# ParticleCounter.net
KiCad netlist of a schematic drawn in EAGLE
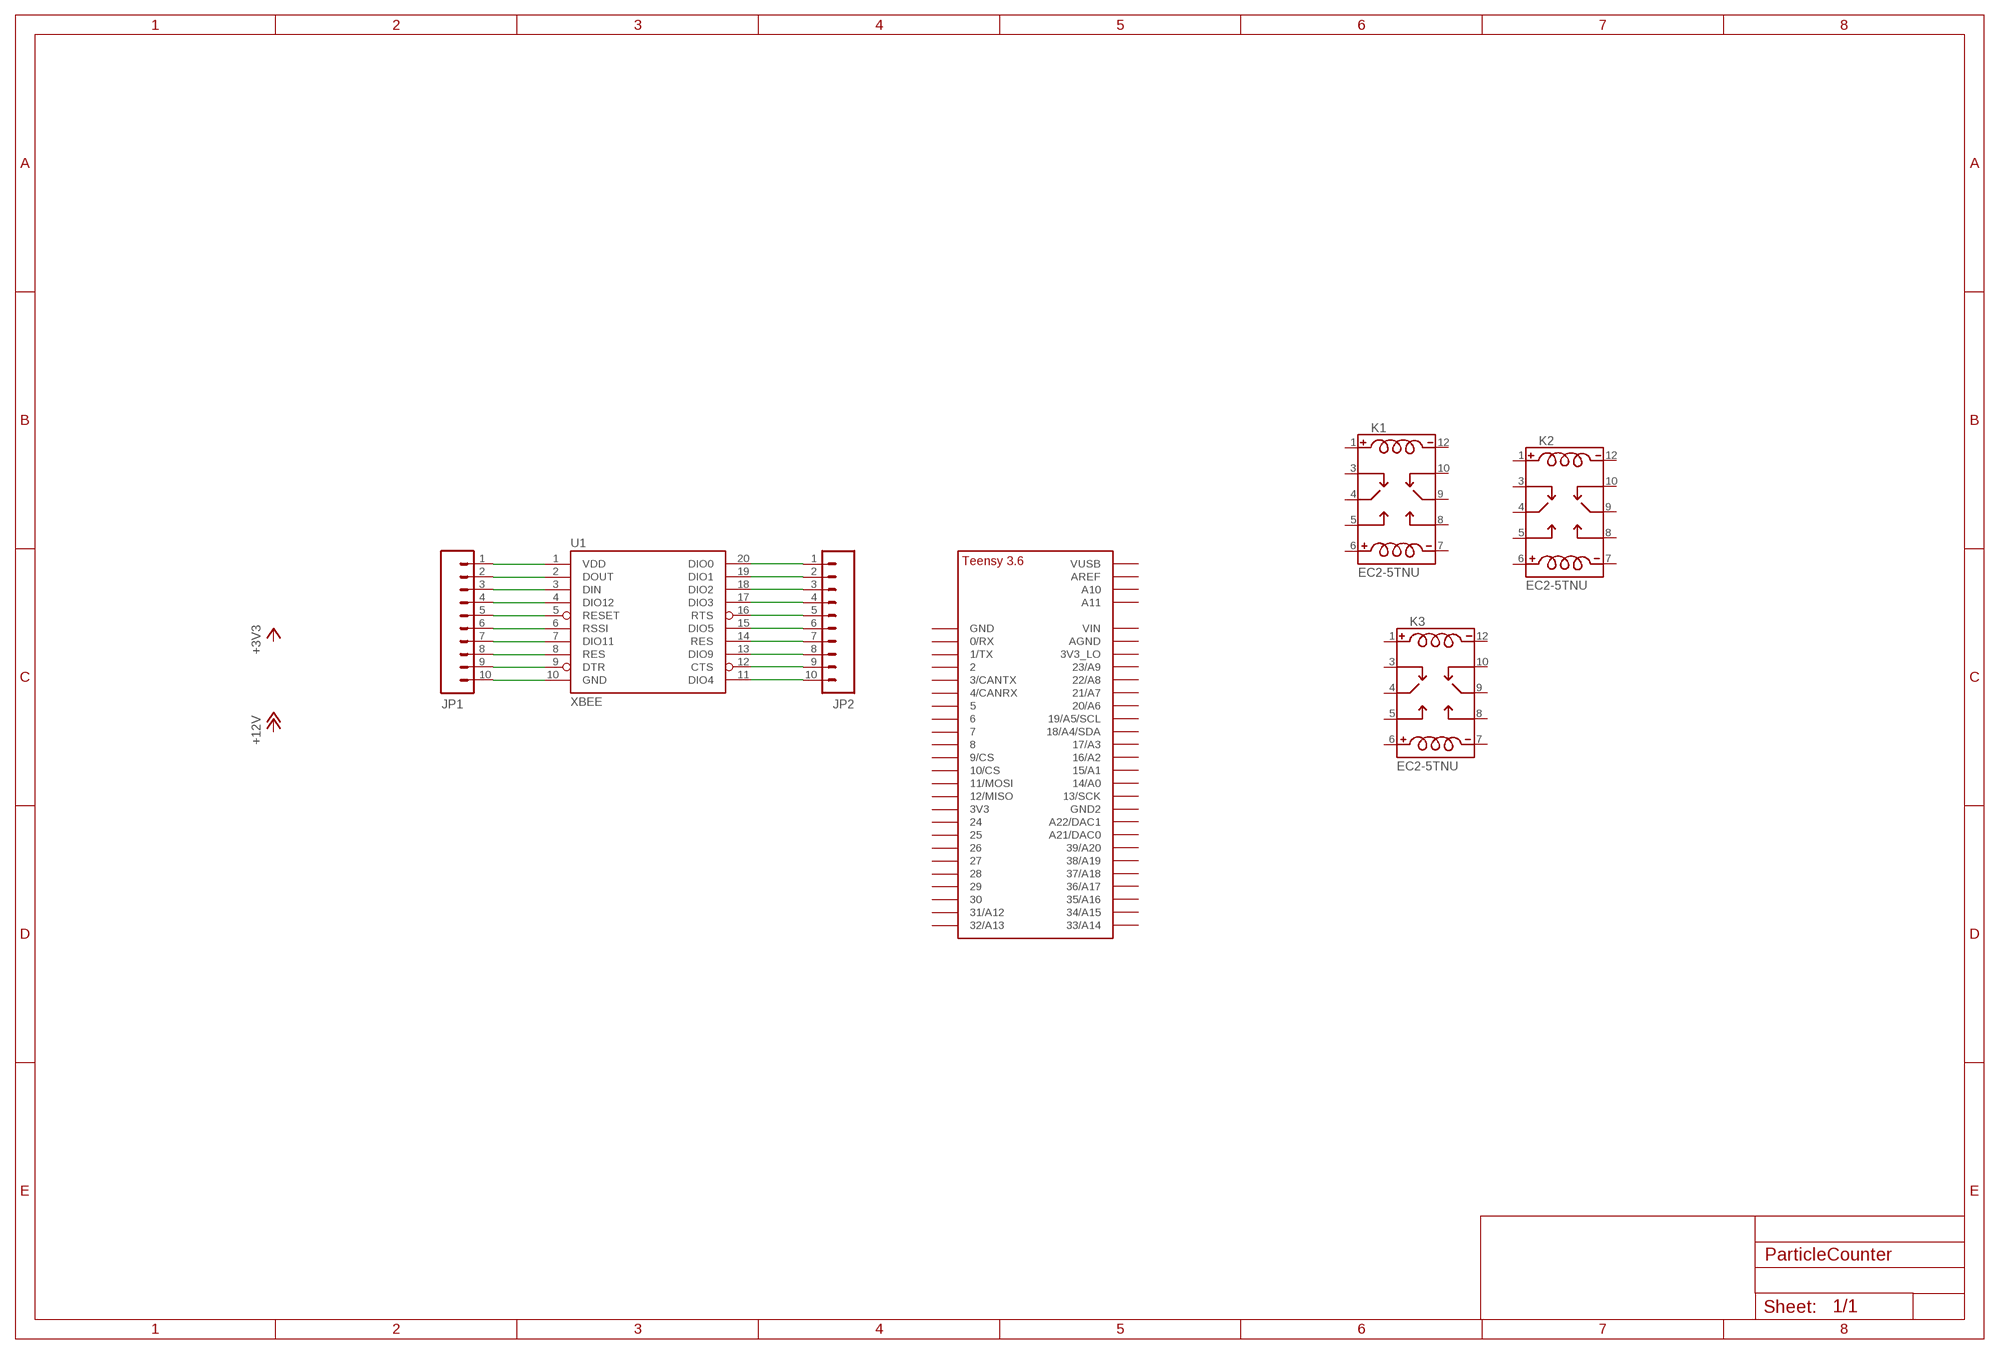
[diagram p0: schematic, sheet 1]

(export (version "E")
  (design (tool "Eeschema 10.0.6"))
  (components
    (comp (ref "JP1")
      (value "M100.1")
      (footprint "eagle-import:1X10")
      (libsource (lib "eagle-import") (part "M100.1"))
    )
    (comp (ref "JP2")
      (value "M100.1")
      (footprint "eagle-import:1X10")
      (libsource (lib "eagle-import") (part "M100.1"))
    )
    (comp (ref "K1")
      (value "EC2-5TNU")
      (footprint "eagle-import:RELAY_EC2-5TNU")
      (fields (field (name "MF") "KEMET"))
      (libsource (lib "eagle-import") (part "EC2-5TNU"))
    )
    (comp (ref "K2")
      (value "EC2-5TNU")
      (footprint "eagle-import:RELAY_EC2-5TNU")
      (fields (field (name "MF") "KEMET"))
      (libsource (lib "eagle-import") (part "EC2-5TNU"))
    )
    (comp (ref "K3")
      (value "EC2-5TNU")
      (footprint "eagle-import:RELAY_EC2-5TNU")
      (fields (field (name "MF") "KEMET"))
      (libsource (lib "eagle-import") (part "EC2-5TNU"))
    )
    (comp (ref "U$1")
      (value "TEENSY_3.5/3.6_BASIC")
      (footprint "eagle-import:TEENSY_3.5_3.6_BASIC")
      (libsource (lib "eagle-import") (part "TEENSY_3.5/3.6_BASIC"))
    )
    (comp (ref "U1")
      (value "XBEE")
      (footprint "eagle-import:XBEE-1")
      (libsource (lib "eagle-import") (part "XBEE-1B1"))
    )
  )
  (nets
    (net (code "3") (name "Net-(JP1-Pad8)") (class "Default")
      (node (ref "JP1") (pin "8") (pinfunction "8_8") (pintype "passive"))
      (node (ref "U1") (pin "8") (pinfunction "RES_8") (pintype "bidirectional"))
    )
    (net (code "4") (name "Net-(JP2-Pad7)") (class "Default")
      (node (ref "JP2") (pin "7") (pinfunction "7_7") (pintype "passive"))
      (node (ref "U1") (pin "14") (pinfunction "RES_14") (pintype "bidirectional"))
    )
    (net (code "5") (name "Net-(U1-CTS)") (class "Default")
      (node (ref "JP2") (pin "9") (pinfunction "9_9") (pintype "passive"))
      (node (ref "U1") (pin "12") (pinfunction "CTS_12") (pintype "output"))
    )
    (net (code "6") (name "Net-(U1-DIN)") (class "Default")
      (node (ref "JP1") (pin "3") (pinfunction "3_3") (pintype "passive"))
      (node (ref "U1") (pin "3") (pinfunction "DIN_3") (pintype "input"))
    )
    (net (code "7") (name "Net-(U1-DIO0)") (class "Default")
      (node (ref "JP2") (pin "1") (pinfunction "1_1") (pintype "passive"))
      (node (ref "U1") (pin "20") (pinfunction "DIO0_20") (pintype "bidirectional"))
    )
    (net (code "8") (name "Net-(U1-DIO1)") (class "Default")
      (node (ref "JP2") (pin "2") (pinfunction "2_2") (pintype "passive"))
      (node (ref "U1") (pin "19") (pinfunction "DIO1_19") (pintype "bidirectional"))
    )
    (net (code "9") (name "Net-(U1-DIO2)") (class "Default")
      (node (ref "JP2") (pin "3") (pinfunction "3_3") (pintype "passive"))
      (node (ref "U1") (pin "18") (pinfunction "DIO2_18") (pintype "bidirectional"))
    )
    (net (code "10") (name "Net-(U1-DIO3)") (class "Default")
      (node (ref "JP2") (pin "4") (pinfunction "4_4") (pintype "passive"))
      (node (ref "U1") (pin "17") (pinfunction "DIO3_17") (pintype "bidirectional"))
    )
    (net (code "11") (name "Net-(U1-DIO4)") (class "Default")
      (node (ref "JP2") (pin "10") (pinfunction "10_10") (pintype "passive"))
      (node (ref "U1") (pin "11") (pinfunction "DIO4_11") (pintype "bidirectional"))
    )
    (net (code "12") (name "Net-(U1-DIO5)") (class "Default")
      (node (ref "JP2") (pin "6") (pinfunction "6_6") (pintype "passive"))
      (node (ref "U1") (pin "15") (pinfunction "DIO5_15") (pintype "bidirectional"))
    )
    (net (code "13") (name "Net-(U1-DIO9)") (class "Default")
      (node (ref "JP2") (pin "8") (pinfunction "8_8") (pintype "passive"))
      (node (ref "U1") (pin "13") (pinfunction "DIO9_13") (pintype "bidirectional"))
    )
    (net (code "14") (name "Net-(U1-DIO11)") (class "Default")
      (node (ref "JP1") (pin "7") (pinfunction "7_7") (pintype "passive"))
      (node (ref "U1") (pin "7") (pinfunction "DIO11_7") (pintype "bidirectional"))
    )
    (net (code "15") (name "Net-(U1-DIO12)") (class "Default")
      (node (ref "JP1") (pin "4") (pinfunction "4_4") (pintype "passive"))
      (node (ref "U1") (pin "4") (pinfunction "DIO12_4") (pintype "bidirectional"))
    )
    (net (code "16") (name "Net-(U1-DOUT)") (class "Default")
      (node (ref "JP1") (pin "2") (pinfunction "2_2") (pintype "passive"))
      (node (ref "U1") (pin "2") (pinfunction "DOUT_2") (pintype "output"))
    )
    (net (code "17") (name "Net-(U1-DTR)") (class "Default")
      (node (ref "JP1") (pin "9") (pinfunction "9_9") (pintype "passive"))
      (node (ref "U1") (pin "9") (pinfunction "DTR_9") (pintype "bidirectional"))
    )
    (net (code "18") (name "Net-(U1-GND)") (class "Default")
      (node (ref "JP1") (pin "10") (pinfunction "10_10") (pintype "passive"))
      (node (ref "U1") (pin "10") (pinfunction "GND_10") (pintype "power_in"))
    )
    (net (code "19") (name "Net-(U1-RESET)") (class "Default")
      (node (ref "JP1") (pin "5") (pinfunction "5_5") (pintype "passive"))
      (node (ref "U1") (pin "5") (pinfunction "RESET_5") (pintype "input"))
    )
    (net (code "20") (name "Net-(U1-RSSI)") (class "Default")
      (node (ref "JP1") (pin "6") (pinfunction "6_6") (pintype "passive"))
      (node (ref "U1") (pin "6") (pinfunction "RSSI_6") (pintype "bidirectional"))
    )
    (net (code "21") (name "Net-(U1-RTS)") (class "Default")
      (node (ref "JP2") (pin "5") (pinfunction "5_5") (pintype "passive"))
      (node (ref "U1") (pin "16") (pinfunction "RTS_16") (pintype "input"))
    )
    (net (code "22") (name "Net-(U1-VDD)") (class "Default")
      (node (ref "JP1") (pin "1") (pinfunction "1_1") (pintype "passive"))
      (node (ref "U1") (pin "1") (pinfunction "VDD_1") (pintype "power_in"))
    )
    (net (code "23") (name "unconnected-(K1-C1-Pad1)") (class "Default")
      (node (ref "K1") (pin "1") (pinfunction "C1_1") (pintype "passive"))
    )
    (net (code "24") (name "unconnected-(K1-C2-Pad12)") (class "Default")
      (node (ref "K1") (pin "12") (pinfunction "C2_12") (pintype "passive"))
    )
    (net (code "25") (name "unconnected-(K1-C3-Pad6)") (class "Default")
      (node (ref "K1") (pin "6") (pinfunction "C3_6") (pintype "passive"))
    )
    (net (code "26") (name "unconnected-(K1-C4-Pad7)") (class "Default")
      (node (ref "K1") (pin "7") (pinfunction "C4_7") (pintype "passive"))
    )
    (net (code "27") (name "unconnected-(K1-M-Pad9)") (class "Default")
      (node (ref "K1") (pin "9") (pinfunction "M_9") (pintype "passive"))
    )
    (net (code "28") (name "unconnected-(K1-M1-Pad4)") (class "Default")
      (node (ref "K1") (pin "4") (pinfunction "M1_4") (pintype "passive"))
    )
    (net (code "29") (name "unconnected-(K1-NC-Pad10)") (class "Default")
      (node (ref "K1") (pin "10") (pinfunction "NC_10") (pintype "passive"))
    )
    (net (code "30") (name "unconnected-(K1-NC1-Pad3)") (class "Default")
      (node (ref "K1") (pin "3") (pinfunction "NC1_3") (pintype "passive"))
    )
    (net (code "31") (name "unconnected-(K1-NO-Pad8)") (class "Default")
      (node (ref "K1") (pin "8") (pinfunction "NO_8") (pintype "passive"))
    )
    (net (code "32") (name "unconnected-(K1-NO1-Pad5)") (class "Default")
      (node (ref "K1") (pin "5") (pinfunction "NO1_5") (pintype "passive"))
    )
    (net (code "33") (name "unconnected-(K2-C1-Pad1)") (class "Default")
      (node (ref "K2") (pin "1") (pinfunction "C1_1") (pintype "passive"))
    )
    (net (code "34") (name "unconnected-(K2-C2-Pad12)") (class "Default")
      (node (ref "K2") (pin "12") (pinfunction "C2_12") (pintype "passive"))
    )
    (net (code "35") (name "unconnected-(K2-C3-Pad6)") (class "Default")
      (node (ref "K2") (pin "6") (pinfunction "C3_6") (pintype "passive"))
    )
    (net (code "36") (name "unconnected-(K2-C4-Pad7)") (class "Default")
      (node (ref "K2") (pin "7") (pinfunction "C4_7") (pintype "passive"))
    )
    (net (code "37") (name "unconnected-(K2-M-Pad9)") (class "Default")
      (node (ref "K2") (pin "9") (pinfunction "M_9") (pintype "passive"))
    )
    (net (code "38") (name "unconnected-(K2-M1-Pad4)") (class "Default")
      (node (ref "K2") (pin "4") (pinfunction "M1_4") (pintype "passive"))
    )
    (net (code "39") (name "unconnected-(K2-NC-Pad10)") (class "Default")
      (node (ref "K2") (pin "10") (pinfunction "NC_10") (pintype "passive"))
    )
    (net (code "40") (name "unconnected-(K2-NC1-Pad3)") (class "Default")
      (node (ref "K2") (pin "3") (pinfunction "NC1_3") (pintype "passive"))
    )
    (net (code "41") (name "unconnected-(K2-NO-Pad8)") (class "Default")
      (node (ref "K2") (pin "8") (pinfunction "NO_8") (pintype "passive"))
    )
    (net (code "42") (name "unconnected-(K2-NO1-Pad5)") (class "Default")
      (node (ref "K2") (pin "5") (pinfunction "NO1_5") (pintype "passive"))
    )
    (net (code "43") (name "unconnected-(K3-C1-Pad1)") (class "Default")
      (node (ref "K3") (pin "1") (pinfunction "C1_1") (pintype "passive"))
    )
    (net (code "44") (name "unconnected-(K3-C2-Pad12)") (class "Default")
      (node (ref "K3") (pin "12") (pinfunction "C2_12") (pintype "passive"))
    )
    (net (code "45") (name "unconnected-(K3-C3-Pad6)") (class "Default")
      (node (ref "K3") (pin "6") (pinfunction "C3_6") (pintype "passive"))
    )
    (net (code "46") (name "unconnected-(K3-C4-Pad7)") (class "Default")
      (node (ref "K3") (pin "7") (pinfunction "C4_7") (pintype "passive"))
    )
    (net (code "47") (name "unconnected-(K3-M-Pad9)") (class "Default")
      (node (ref "K3") (pin "9") (pinfunction "M_9") (pintype "passive"))
    )
    (net (code "48") (name "unconnected-(K3-M1-Pad4)") (class "Default")
      (node (ref "K3") (pin "4") (pinfunction "M1_4") (pintype "passive"))
    )
    (net (code "49") (name "unconnected-(K3-NC-Pad10)") (class "Default")
      (node (ref "K3") (pin "10") (pinfunction "NC_10") (pintype "passive"))
    )
    (net (code "50") (name "unconnected-(K3-NC1-Pad3)") (class "Default")
      (node (ref "K3") (pin "3") (pinfunction "NC1_3") (pintype "passive"))
    )
    (net (code "51") (name "unconnected-(K3-NO-Pad8)") (class "Default")
      (node (ref "K3") (pin "8") (pinfunction "NO_8") (pintype "passive"))
    )
    (net (code "52") (name "unconnected-(K3-NO1-Pad5)") (class "Default")
      (node (ref "K3") (pin "5") (pinfunction "NO1_5") (pintype "passive"))
    )
    (net (code "53") (name "unconnected-(U$1-A21{slash}DAC0-Pad21{slash}DAC0)") (class "Default")
      (node (ref "U$1") (pin "21/DAC0") (pinfunction "A21/DAC0_21/DAC0") (pintype "bidirectional"))
    )
    (net (code "54") (name "unconnected-(U$1-Pad0{slash}RX)") (class "Default")
      (node (ref "U$1") (pin "0/RX") (pinfunction "0/RX_0/RX") (pintype "bidirectional"))
    )
    (net (code "55") (name "unconnected-(U$1-Pad1{slash}TX)") (class "Default")
      (node (ref "U$1") (pin "1/TX") (pinfunction "1/TX_1/TX") (pintype "bidirectional"))
    )
    (net (code "56") (name "unconnected-(U$1-Pad2)") (class "Default")
      (node (ref "U$1") (pin "2") (pinfunction "2_2") (pintype "bidirectional"))
    )
    (net (code "57") (name "unconnected-(U$1-Pad3V3)") (class "Default")
      (node (ref "U$1") (pin "3V3") (pinfunction "3V3_3V3") (pintype "bidirectional"))
    )
    (net (code "58") (name "unconnected-(U$1-Pad3V3_LO)") (class "Default")
      (node (ref "U$1") (pin "3V3_LO") (pinfunction "3V3_LO_3V3_LO") (pintype "bidirectional"))
    )
    (net (code "59") (name "unconnected-(U$1-Pad3{slash}CANTX)") (class "Default")
      (node (ref "U$1") (pin "3/CANTX") (pinfunction "3/CANTX_3/CANTX") (pintype "bidirectional"))
    )
    (net (code "60") (name "unconnected-(U$1-Pad4{slash}CANRX)") (class "Default")
      (node (ref "U$1") (pin "4/CANRX") (pinfunction "4/CANRX_4/CANRX") (pintype "bidirectional"))
    )
    (net (code "61") (name "unconnected-(U$1-Pad5)") (class "Default")
      (node (ref "U$1") (pin "5") (pinfunction "5_5") (pintype "bidirectional"))
    )
    (net (code "62") (name "unconnected-(U$1-Pad6)") (class "Default")
      (node (ref "U$1") (pin "6") (pinfunction "6_6") (pintype "bidirectional"))
    )
    (net (code "63") (name "unconnected-(U$1-Pad7)") (class "Default")
      (node (ref "U$1") (pin "7") (pinfunction "7_7") (pintype "bidirectional"))
    )
    (net (code "64") (name "unconnected-(U$1-Pad8)") (class "Default")
      (node (ref "U$1") (pin "8") (pinfunction "8_8") (pintype "bidirectional"))
    )
    (net (code "65") (name "unconnected-(U$1-Pad9{slash}CS)") (class "Default")
      (node (ref "U$1") (pin "9/CS") (pinfunction "9/CS_9/CS") (pintype "bidirectional"))
    )
    (net (code "66") (name "unconnected-(U$1-Pad10{slash}CS)") (class "Default")
      (node (ref "U$1") (pin "10/CS") (pinfunction "10/CS_10/CS") (pintype "bidirectional"))
    )
    (net (code "67") (name "unconnected-(U$1-Pad11{slash}MOSI)") (class "Default")
      (node (ref "U$1") (pin "11/MOSI") (pinfunction "11/MOSI_11/MOSI") (pintype "bidirectional"))
    )
    (net (code "68") (name "unconnected-(U$1-Pad12{slash}MISO)") (class "Default")
      (node (ref "U$1") (pin "12/MISO") (pinfunction "12/MISO_12/MISO") (pintype "bidirectional"))
    )
    (net (code "69") (name "unconnected-(U$1-Pad13{slash}SCK)") (class "Default")
      (node (ref "U$1") (pin "13/SCK") (pinfunction "13/SCK_13/SCK") (pintype "bidirectional"))
    )
    (net (code "70") (name "unconnected-(U$1-Pad14{slash}A0)") (class "Default")
      (node (ref "U$1") (pin "14/A0") (pinfunction "14/A0_14/A0") (pintype "bidirectional"))
    )
    (net (code "71") (name "unconnected-(U$1-Pad15{slash}A1)") (class "Default")
      (node (ref "U$1") (pin "15/A1") (pinfunction "15/A1_15/A1") (pintype "bidirectional"))
    )
    (net (code "72") (name "unconnected-(U$1-Pad16{slash}A2)") (class "Default")
      (node (ref "U$1") (pin "16/A2") (pinfunction "16/A2_16/A2") (pintype "bidirectional"))
    )
    (net (code "73") (name "unconnected-(U$1-Pad17{slash}A3)") (class "Default")
      (node (ref "U$1") (pin "17/A3") (pinfunction "17/A3_17/A3") (pintype "bidirectional"))
    )
    (net (code "74") (name "unconnected-(U$1-Pad18{slash}A4{slash}SDA)") (class "Default")
      (node (ref "U$1") (pin "18/A4/SDA") (pinfunction "18/A4/SDA_18/A4/SDA") (pintype "bidirectional"))
    )
    (net (code "75") (name "unconnected-(U$1-Pad19{slash}A5{slash}SCL)") (class "Default")
      (node (ref "U$1") (pin "19/A5/SCL") (pinfunction "19/A5/SCL_19/A5/SCL") (pintype "bidirectional"))
    )
    (net (code "76") (name "unconnected-(U$1-Pad20{slash}A6)") (class "Default")
      (node (ref "U$1") (pin "20/A6") (pinfunction "20/A6_20/A6") (pintype "bidirectional"))
    )
    (net (code "77") (name "unconnected-(U$1-Pad21{slash}A7)") (class "Default")
      (node (ref "U$1") (pin "21/A7") (pinfunction "21/A7_21/A7") (pintype "bidirectional"))
    )
    (net (code "78") (name "unconnected-(U$1-Pad22{slash}A8)") (class "Default")
      (node (ref "U$1") (pin "22/A8") (pinfunction "22/A8_22/A8") (pintype "bidirectional"))
    )
    (net (code "79") (name "unconnected-(U$1-Pad23{slash}A9)") (class "Default")
      (node (ref "U$1") (pin "23/A9") (pinfunction "23/A9_23/A9") (pintype "bidirectional"))
    )
    (net (code "80") (name "unconnected-(U$1-Pad24)") (class "Default")
      (node (ref "U$1") (pin "24") (pinfunction "24_24") (pintype "bidirectional"))
    )
    (net (code "81") (name "unconnected-(U$1-Pad25)") (class "Default")
      (node (ref "U$1") (pin "25") (pinfunction "25_25") (pintype "bidirectional"))
    )
    (net (code "82") (name "unconnected-(U$1-Pad26)") (class "Default")
      (node (ref "U$1") (pin "26") (pinfunction "26_26") (pintype "bidirectional"))
    )
    (net (code "83") (name "unconnected-(U$1-Pad27)") (class "Default")
      (node (ref "U$1") (pin "27") (pinfunction "27_27") (pintype "bidirectional"))
    )
    (net (code "84") (name "unconnected-(U$1-Pad28)") (class "Default")
      (node (ref "U$1") (pin "28") (pinfunction "28_28") (pintype "bidirectional"))
    )
    (net (code "85") (name "unconnected-(U$1-Pad29)") (class "Default")
      (node (ref "U$1") (pin "29") (pinfunction "29_29") (pintype "bidirectional"))
    )
    (net (code "86") (name "unconnected-(U$1-Pad30)") (class "Default")
      (node (ref "U$1") (pin "30") (pinfunction "30_30") (pintype "bidirectional"))
    )
    (net (code "87") (name "unconnected-(U$1-Pad31{slash}A12)") (class "Default")
      (node (ref "U$1") (pin "31/A12") (pinfunction "31/A12_31/A12") (pintype "bidirectional"))
    )
    (net (code "88") (name "unconnected-(U$1-Pad32{slash}A13)") (class "Default")
      (node (ref "U$1") (pin "32/A13") (pinfunction "32/A13_32/A13") (pintype "bidirectional"))
    )
    (net (code "89") (name "unconnected-(U$1-Pad33{slash}A14)") (class "Default")
      (node (ref "U$1") (pin "33/A14") (pinfunction "33/A14_33/A14") (pintype "bidirectional"))
    )
    (net (code "90") (name "unconnected-(U$1-Pad34{slash}A15)") (class "Default")
      (node (ref "U$1") (pin "34/A15") (pinfunction "34/A15_34/A15") (pintype "bidirectional"))
    )
    (net (code "91") (name "unconnected-(U$1-Pad35{slash}A16)") (class "Default")
      (node (ref "U$1") (pin "35/A16") (pinfunction "35/A16_35/A16") (pintype "bidirectional"))
    )
    (net (code "92") (name "unconnected-(U$1-Pad36{slash}A17)") (class "Default")
      (node (ref "U$1") (pin "36/A17") (pinfunction "36/A17_36/A17") (pintype "bidirectional"))
    )
    (net (code "93") (name "unconnected-(U$1-Pad37{slash}A18)") (class "Default")
      (node (ref "U$1") (pin "37/A18") (pinfunction "37/A18_37/A18") (pintype "bidirectional"))
    )
    (net (code "94") (name "unconnected-(U$1-Pad38{slash}A19)") (class "Default")
      (node (ref "U$1") (pin "38/A19") (pinfunction "38/A19_38/A19") (pintype "bidirectional"))
    )
    (net (code "95") (name "unconnected-(U$1-Pad39{slash}A20)") (class "Default")
      (node (ref "U$1") (pin "39/A20") (pinfunction "39/A20_39/A20") (pintype "bidirectional"))
    )
    (net (code "96") (name "unconnected-(U$1-PadA10)") (class "Default")
      (node (ref "U$1") (pin "A10") (pinfunction "A10_A10") (pintype "bidirectional"))
    )
    (net (code "97") (name "unconnected-(U$1-PadA11)") (class "Default")
      (node (ref "U$1") (pin "A11") (pinfunction "A11_A11") (pintype "bidirectional"))
    )
    (net (code "98") (name "unconnected-(U$1-PadA22{slash}DAC1)") (class "Default")
      (node (ref "U$1") (pin "A22/DAC1") (pinfunction "A22/DAC1_A22/DAC1") (pintype "bidirectional"))
    )
    (net (code "99") (name "unconnected-(U$1-PadAGND)") (class "Default")
      (node (ref "U$1") (pin "AGND") (pinfunction "AGND_AGND") (pintype "bidirectional"))
    )
    (net (code "100") (name "unconnected-(U$1-PadAREF)") (class "Default")
      (node (ref "U$1") (pin "AREF") (pinfunction "AREF_AREF") (pintype "bidirectional"))
    )
    (net (code "101") (name "unconnected-(U$1-PadGND)") (class "Default")
      (node (ref "U$1") (pin "GND") (pinfunction "GND_GND") (pintype "bidirectional"))
    )
    (net (code "102") (name "unconnected-(U$1-PadGND2)") (class "Default")
      (node (ref "U$1") (pin "GND2") (pinfunction "GND2_GND2") (pintype "bidirectional"))
    )
    (net (code "103") (name "unconnected-(U$1-PadVIN)") (class "Default")
      (node (ref "U$1") (pin "VIN") (pinfunction "VIN_VIN") (pintype "bidirectional"))
    )
    (net (code "104") (name "unconnected-(U$1-PadVUSB)") (class "Default")
      (node (ref "U$1") (pin "VUSB") (pinfunction "VUSB_VUSB") (pintype "bidirectional"))
    )
  )
)
